# 14_-_LTC3676.net
KiCad netlist of a schematic drawn in Altium Designer
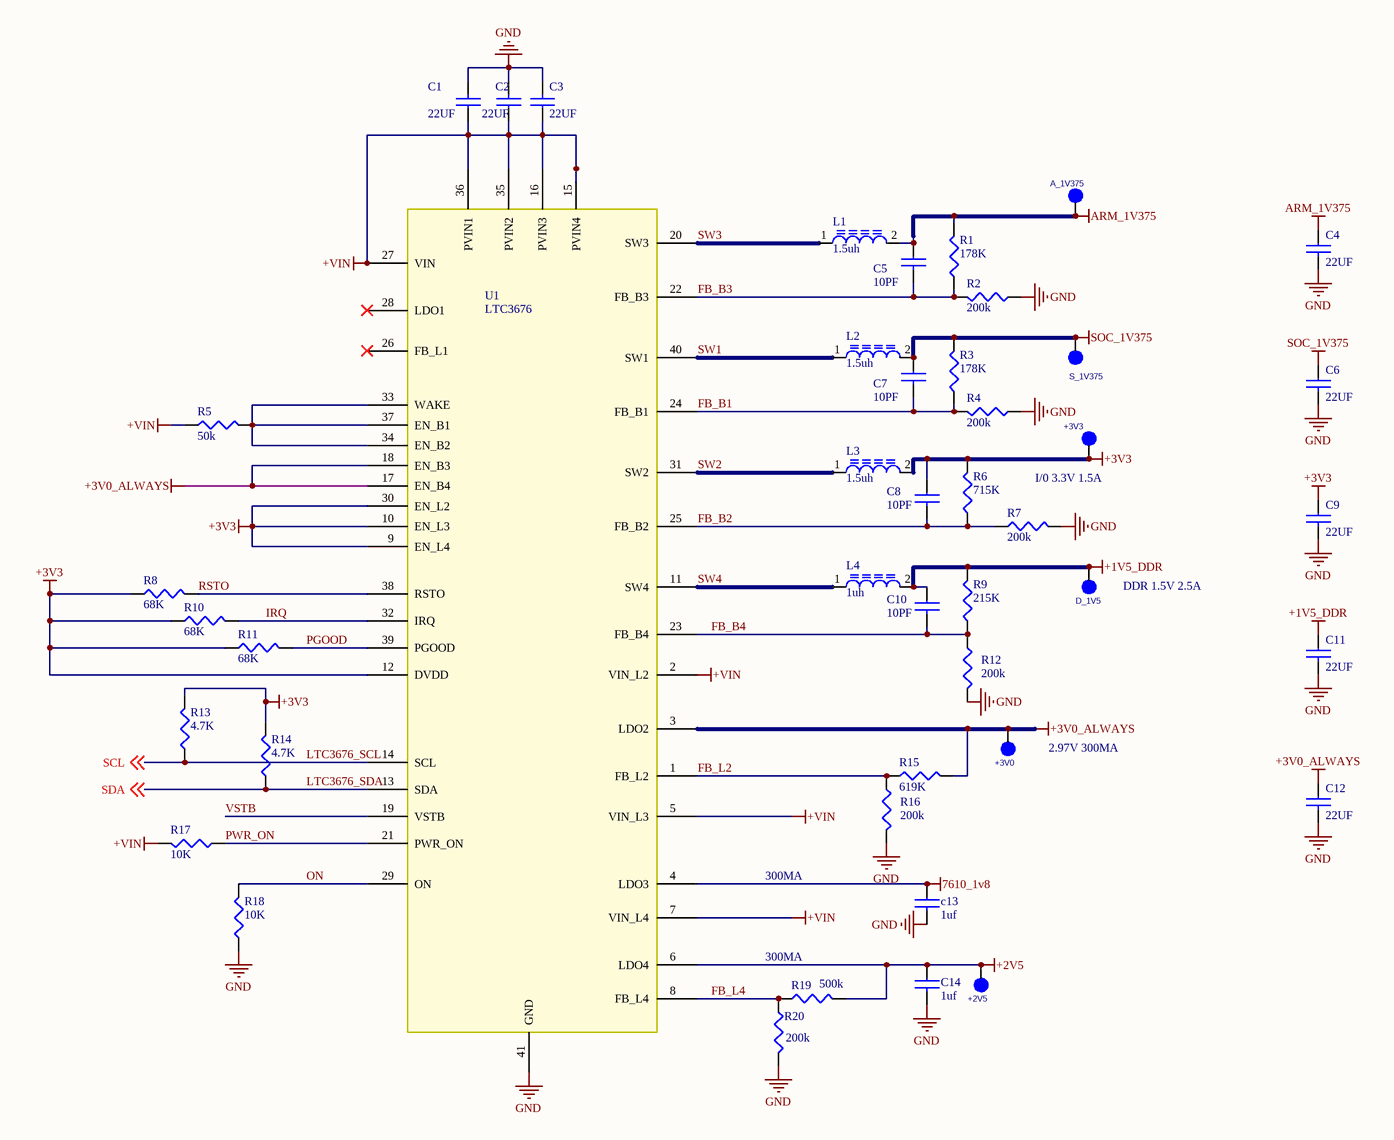
[diagram p0: [14] - LTC3676.SchDoc]

(export (version "E")
  (design (tool "Eeschema 10.0.6"))
  (components
    (comp (ref "+2V5")
      (value "~")
      (description "TEST POINT PAD 0.5MM DIA SMT, NO PART TO ORDER")
      (libsource (lib "*") (part "TESTLOOP"))
    )
    (comp (ref "+3V0")
      (value "~")
      (description "TEST POINT PAD 0.5MM DIA SMT, NO PART TO ORDER")
      (libsource (lib "*") (part "TESTLOOP"))
    )
    (comp (ref "+3V3")
      (value "~")
      (description "TEST POINT PAD 0.5MM DIA SMT, NO PART TO ORDER")
      (libsource (lib "*") (part "TESTLOOP"))
    )
    (comp (ref "A_1V375")
      (value "~")
      (description "TEST POINT PAD 0.5MM DIA SMT, NO PART TO ORDER")
      (libsource (lib "*") (part "TESTLOOP"))
    )
    (comp (ref "C1")
      (value "22UF")
      (footprint "C1206A")
      (description "CAP CER 100UF 10V X5R 20% 1206")
      (fields
        (field (name "MANUFACTURER") "TDK Corporation")
        (field (name "MANUFACTURER PART NUMBER") "C3216X5R1A107M")
      )
      (libsource (lib "Integrated_Library_RF_FEB_2012") (part "C3216X5R1A107M"))
    )
    (comp (ref "C2")
      (value "22UF")
      (footprint "C1206A")
      (description "CAP CER 100UF 10V X5R 20% 1206")
      (fields
        (field (name "MANUFACTURER") "TDK Corporation")
        (field (name "MANUFACTURER PART NUMBER") "C3216X5R1A107M")
      )
      (libsource (lib "Integrated_Library_RF_FEB_2012") (part "C3216X5R1A107M"))
    )
    (comp (ref "C3")
      (value "22UF")
      (footprint "C1206A")
      (description "CAP CER 100UF 10V X5R 20% 1206")
      (fields
        (field (name "MANUFACTURER") "TDK Corporation")
        (field (name "MANUFACTURER PART NUMBER") "C3216X5R1A107M")
      )
      (libsource (lib "Integrated_Library_RF_FEB_2012") (part "C3216X5R1A107M"))
    )
    (comp (ref "C4")
      (value "22UF")
      (footprint "7343CAP")
      (description "CAP CER 100UF 10V X5R 20% 1206")
      (fields
        (field (name "MANUFACTURER") "TDK Corporation")
        (field (name "MANUFACTURER PART NUMBER") "C3216X5R1A107M")
      )
      (libsource (lib "Integrated_Library_RF_FEB_2012") (part "C3216X5R1A107M"))
    )
    (comp (ref "C5")
      (value "10PF")
      (footprint "C0402")
      (description "CAP CER .22UF 25V X5R 20% 0402")
      (fields
        (field (name "MANUFACTURER") "TDK Corporation")
        (field (name "MANUFACTURER PART NUMBER") "C1005X5R1E224M")
      )
      (libsource (lib "Integrated_Library_RF_FEB_2012") (part "C1005X5R1E224M"))
    )
    (comp (ref "C6")
      (value "22UF")
      (footprint "C1206A")
      (description "CAP CER 100UF 10V X5R 20% 1206")
      (fields
        (field (name "MANUFACTURER") "TDK Corporation")
        (field (name "MANUFACTURER PART NUMBER") "C3216X5R1A107M")
      )
      (libsource (lib "Integrated_Library_RF_FEB_2012") (part "C3216X5R1A107M"))
    )
    (comp (ref "C7")
      (value "10PF")
      (footprint "C0402")
      (description "CAP CER .22UF 25V X5R 20% 0402")
      (fields
        (field (name "MANUFACTURER") "TDK Corporation")
        (field (name "MANUFACTURER PART NUMBER") "C1005X5R1E224M")
      )
      (libsource (lib "Integrated_Library_RF_FEB_2012") (part "C1005X5R1E224M"))
    )
    (comp (ref "C8")
      (value "10PF")
      (footprint "C0402")
      (description "CAP CER .22UF 25V X5R 20% 0402")
      (fields
        (field (name "MANUFACTURER") "TDK Corporation")
        (field (name "MANUFACTURER PART NUMBER") "C1005X5R1E224M")
      )
      (libsource (lib "Integrated_Library_RF_FEB_2012") (part "C1005X5R1E224M"))
    )
    (comp (ref "C9")
      (value "22UF")
      (footprint "C1206A")
      (description "CAP CER 100UF 10V X5R 20% 1206")
      (fields
        (field (name "MANUFACTURER") "TDK Corporation")
        (field (name "MANUFACTURER PART NUMBER") "C3216X5R1A107M")
      )
      (libsource (lib "Integrated_Library_RF_FEB_2012") (part "C3216X5R1A107M"))
    )
    (comp (ref "C10")
      (value "10PF")
      (footprint "C0402")
      (description "CAP CER .22UF 25V X5R 20% 0402")
      (fields
        (field (name "MANUFACTURER") "TDK Corporation")
        (field (name "MANUFACTURER PART NUMBER") "C1005X5R1E224M")
      )
      (libsource (lib "Integrated_Library_RF_FEB_2012") (part "C1005X5R1E224M"))
    )
    (comp (ref "C11")
      (value "22UF")
      (footprint "C1206A")
      (description "CAP CER 100UF 10V X5R 20% 1206")
      (fields
        (field (name "MANUFACTURER") "TDK Corporation")
        (field (name "MANUFACTURER PART NUMBER") "C3216X5R1A107M")
      )
      (libsource (lib "Integrated_Library_RF_FEB_2012") (part "C3216X5R1A107M"))
    )
    (comp (ref "C12")
      (value "22UF")
      (footprint "C1206A")
      (description "CAP CER 100UF 10V X5R 20% 1206")
      (fields
        (field (name "MANUFACTURER") "TDK Corporation")
        (field (name "MANUFACTURER PART NUMBER") "C3216X5R1A107M")
      )
      (libsource (lib "Integrated_Library_RF_FEB_2012") (part "C3216X5R1A107M"))
    )
    (comp (ref "c13")
      (value "1uf")
      (footprint "C0402")
      (description "CAP CER .22UF 25V X5R 20% 0402")
      (fields
        (field (name "MANUFACTURER") "TDK Corporation")
        (field (name "MANUFACTURER PART NUMBER") "C1005X5R1E224M")
      )
      (libsource (lib "Integrated_Library_RF_FEB_2012") (part "C1005X5R1E224M"))
    )
    (comp (ref "C14")
      (value "1uf")
      (footprint "C0402")
      (description "CAP CER .22UF 25V X5R 20% 0402")
      (fields
        (field (name "MANUFACTURER") "TDK Corporation")
        (field (name "MANUFACTURER PART NUMBER") "C1005X5R1E224M")
      )
      (libsource (lib "Integrated_Library_RF_FEB_2012") (part "C1005X5R1E224M"))
    )
    (comp (ref "D_1V5")
      (value "~")
      (description "TEST POINT PAD 0.5MM DIA SMT, NO PART TO ORDER")
      (libsource (lib "*") (part "TESTLOOP"))
    )
    (comp (ref "L1")
      (value "1.5uh")
      (footprint "VLCF4020")
      (description "INDUCTOR POWER 10UH .85A SMD")
      (fields
        (field (name "MANUFACTURER") "TDK Corporation")
        (field (name "MANUFACTURER PART NUMBER") "VLCF4020T-100MR85")
        (field (name ".CREATOR") "MM")
        (field (name ".CHECKED PCB") "MM, checked by RF")
        (field (name ".CHECKED SCH") "MM, checked by RF")
      )
      (libsource (lib "Schlib_RF") (part "VLCF4020T-100MR85"))
    )
    (comp (ref "L2")
      (value "1.5uh")
      (footprint "VLCF4020")
      (description "INDUCTOR POWER 10UH .85A SMD")
      (fields
        (field (name "MANUFACTURER") "TDK Corporation")
        (field (name "MANUFACTURER PART NUMBER") "VLCF4020T-100MR85")
        (field (name ".CREATOR") "MM")
        (field (name ".CHECKED PCB") "MM, checked by RF")
        (field (name ".CHECKED SCH") "MM, checked by RF")
      )
      (libsource (lib "Schlib_RF") (part "VLCF4020T-100MR85"))
    )
    (comp (ref "L3")
      (value "1.5uh")
      (footprint "VLCF4020")
      (description "INDUCTOR POWER 10UH .85A SMD")
      (fields
        (field (name "MANUFACTURER") "TDK Corporation")
        (field (name "MANUFACTURER PART NUMBER") "VLCF4020T-100MR85")
        (field (name ".CREATOR") "MM")
        (field (name ".CHECKED PCB") "MM, checked by RF")
        (field (name ".CHECKED SCH") "MM, checked by RF")
      )
      (libsource (lib "Schlib_RF") (part "VLCF4020T-100MR85"))
    )
    (comp (ref "L4")
      (value "1uh")
      (footprint "VLCF4020")
      (description "INDUCTOR POWER 10UH .85A SMD")
      (fields
        (field (name "MANUFACTURER") "TDK Corporation")
        (field (name "MANUFACTURER PART NUMBER") "VLCF4020T-100MR85")
        (field (name ".CREATOR") "MM")
        (field (name ".CHECKED PCB") "MM, checked by RF")
        (field (name ".CHECKED SCH") "MM, checked by RF")
      )
      (libsource (lib "Schlib_RF") (part "VLCF4020T-100MR85"))
    )
    (comp (ref "R1")
      (value "178K")
      (footprint "R0402")
      (description "RES 39.0K OHM 1/16W 1% 0402 SMD")
      (fields
        (field (name "MANUFACTURER") "Yageo")
        (field (name "MANUFACTURER PART NUMBER") "RC0402FR-0739KL")
      )
      (libsource (lib "Integrated_Library_RF_FEB_2012") (part "RC0402FR-0739KL"))
    )
    (comp (ref "R2")
      (value "200k")
      (footprint "R0402")
      (description "RES 39.0K OHM 1/16W 1% 0402 SMD")
      (fields
        (field (name "MANUFACTURER") "Yageo")
        (field (name "MANUFACTURER PART NUMBER") "RC0402FR-0739KL")
      )
      (libsource (lib "Integrated_Library_RF_FEB_2012") (part "RC0402FR-0739KL"))
    )
    (comp (ref "R3")
      (value "178K")
      (footprint "R0402")
      (description "RES 39.0K OHM 1/16W 1% 0402 SMD")
      (fields
        (field (name "MANUFACTURER") "Yageo")
        (field (name "MANUFACTURER PART NUMBER") "RC0402FR-0739KL")
      )
      (libsource (lib "Integrated_Library_RF_FEB_2012") (part "RC0402FR-0739KL"))
    )
    (comp (ref "R4")
      (value "200k")
      (footprint "R0402")
      (description "RES 39.0K OHM 1/16W 1% 0402 SMD")
      (fields
        (field (name "MANUFACTURER") "Yageo")
        (field (name "MANUFACTURER PART NUMBER") "RC0402FR-0739KL")
      )
      (libsource (lib "Integrated_Library_RF_FEB_2012") (part "RC0402FR-0739KL"))
    )
    (comp (ref "R5")
      (value "50k")
      (footprint "R0402")
      (description "RES 39.0K OHM 1/16W 1% 0402 SMD")
      (fields
        (field (name "MANUFACTURER") "Yageo")
        (field (name "MANUFACTURER PART NUMBER") "RC0402FR-0739KL")
      )
      (libsource (lib "Integrated_Library_RF_FEB_2012") (part "RC0402FR-0739KL"))
    )
    (comp (ref "R6")
      (value "715K")
      (footprint "R0402")
      (description "RES 39.0K OHM 1/16W 1% 0402 SMD")
      (fields
        (field (name "MANUFACTURER") "Yageo")
        (field (name "MANUFACTURER PART NUMBER") "RC0402FR-0739KL")
      )
      (libsource (lib "Integrated_Library_RF_FEB_2012") (part "RC0402FR-0739KL"))
    )
    (comp (ref "R7")
      (value "200k")
      (footprint "R0402")
      (description "RES 39.0K OHM 1/16W 1% 0402 SMD")
      (fields
        (field (name "MANUFACTURER") "Yageo")
        (field (name "MANUFACTURER PART NUMBER") "RC0402FR-0739KL")
      )
      (libsource (lib "Integrated_Library_RF_FEB_2012") (part "RC0402FR-0739KL"))
    )
    (comp (ref "R8")
      (value "68K")
      (footprint "R0402")
      (description "RES 39.0K OHM 1/16W 1% 0402 SMD")
      (fields
        (field (name "MANUFACTURER") "Yageo")
        (field (name "MANUFACTURER PART NUMBER") "RC0402FR-0739KL")
      )
      (libsource (lib "Integrated_Library_RF_FEB_2012") (part "RC0402FR-0739KL"))
    )
    (comp (ref "R9")
      (value "215K")
      (footprint "R0402")
      (description "RES 39.0K OHM 1/16W 1% 0402 SMD")
      (fields
        (field (name "MANUFACTURER") "Yageo")
        (field (name "MANUFACTURER PART NUMBER") "RC0402FR-0739KL")
      )
      (libsource (lib "Integrated_Library_RF_FEB_2012") (part "RC0402FR-0739KL"))
    )
    (comp (ref "R10")
      (value "68K")
      (footprint "R0402")
      (description "RES 39.0K OHM 1/16W 1% 0402 SMD")
      (fields
        (field (name "MANUFACTURER") "Yageo")
        (field (name "MANUFACTURER PART NUMBER") "RC0402FR-0739KL")
      )
      (libsource (lib "Integrated_Library_RF_FEB_2012") (part "RC0402FR-0739KL"))
    )
    (comp (ref "R11")
      (value "68K")
      (footprint "R0402")
      (description "RES 39.0K OHM 1/16W 1% 0402 SMD")
      (fields
        (field (name "MANUFACTURER") "Yageo")
        (field (name "MANUFACTURER PART NUMBER") "RC0402FR-0739KL")
      )
      (libsource (lib "Integrated_Library_RF_FEB_2012") (part "RC0402FR-0739KL"))
    )
    (comp (ref "R12")
      (value "200k")
      (footprint "R0402")
      (description "RES 39.0K OHM 1/16W 1% 0402 SMD")
      (fields
        (field (name "MANUFACTURER") "Yageo")
        (field (name "MANUFACTURER PART NUMBER") "RC0402FR-0739KL")
      )
      (libsource (lib "Integrated_Library_RF_FEB_2012") (part "RC0402FR-0739KL"))
    )
    (comp (ref "R13")
      (value "4.7K")
      (footprint "R0402")
      (description "RES 39.0K OHM 1/16W 1% 0402 SMD")
      (fields
        (field (name "MANUFACTURER") "Yageo")
        (field (name "MANUFACTURER PART NUMBER") "RC0402FR-0739KL")
      )
      (libsource (lib "Integrated_Library_RF_FEB_2012") (part "RC0402FR-0739KL"))
    )
    (comp (ref "R14")
      (value "4.7K")
      (footprint "R0402")
      (description "RES 39.0K OHM 1/16W 1% 0402 SMD")
      (fields
        (field (name "MANUFACTURER") "Yageo")
        (field (name "MANUFACTURER PART NUMBER") "RC0402FR-0739KL")
      )
      (libsource (lib "Integrated_Library_RF_FEB_2012") (part "RC0402FR-0739KL"))
    )
    (comp (ref "R15")
      (value "619K")
      (footprint "R0402")
      (description "RES 39.0K OHM 1/16W 1% 0402 SMD")
      (fields
        (field (name "MANUFACTURER") "Yageo")
        (field (name "MANUFACTURER PART NUMBER") "RC0402FR-0739KL")
      )
      (libsource (lib "Integrated_Library_RF_FEB_2012") (part "RC0402FR-0739KL"))
    )
    (comp (ref "R16")
      (value "200k")
      (footprint "R0402")
      (description "RES 39.0K OHM 1/16W 1% 0402 SMD")
      (fields
        (field (name "MANUFACTURER") "Yageo")
        (field (name "MANUFACTURER PART NUMBER") "RC0402FR-0739KL")
      )
      (libsource (lib "Integrated_Library_RF_FEB_2012") (part "RC0402FR-0739KL"))
    )
    (comp (ref "R17")
      (value "10K")
      (footprint "R0402")
      (description "RES 39.0K OHM 1/16W 1% 0402 SMD")
      (fields
        (field (name "MANUFACTURER") "Yageo")
        (field (name "MANUFACTURER PART NUMBER") "RC0402FR-0739KL")
      )
      (libsource (lib "Integrated_Library_RF_FEB_2012") (part "RC0402FR-0739KL"))
    )
    (comp (ref "R18")
      (value "10K")
      (footprint "R0402")
      (description "RES 39.0K OHM 1/16W 1% 0402 SMD")
      (fields
        (field (name "MANUFACTURER") "Yageo")
        (field (name "MANUFACTURER PART NUMBER") "RC0402FR-0739KL")
      )
      (libsource (lib "Integrated_Library_RF_FEB_2012") (part "RC0402FR-0739KL"))
    )
    (comp (ref "R19")
      (value "500k")
      (footprint "R0402")
      (description "RES 39.0K OHM 1/16W 1% 0402 SMD")
      (fields
        (field (name "MANUFACTURER") "Yageo")
        (field (name "MANUFACTURER PART NUMBER") "RC0402FR-0739KL")
      )
      (libsource (lib "Integrated_Library_RF_FEB_2012") (part "RC0402FR-0739KL"))
    )
    (comp (ref "R20")
      (value "200k")
      (footprint "R0402")
      (description "RES 39.0K OHM 1/16W 1% 0402 SMD")
      (fields
        (field (name "MANUFACTURER") "Yageo")
        (field (name "MANUFACTURER PART NUMBER") "RC0402FR-0739KL")
      )
      (libsource (lib "Integrated_Library_RF_FEB_2012") (part "RC0402FR-0739KL"))
    )
    (comp (ref "S_1V375")
      (value "~")
      (description "TEST POINT PAD 0.5MM DIA SMT, NO PART TO ORDER")
      (libsource (lib "*") (part "TESTLOOP"))
    )
    (comp (ref "U1") (value "LTC3676") (footprint "qfn40") (libsource (lib "hack") (part "LTC3676")))
  )
  (nets
    (net (code "1") (name "+1V5_DDR") (class "Default")
      (node (ref "C10") (pin "1") (pinfunction "1_1") (pintype "passive"))
      (node (ref "C11") (pin "1") (pinfunction "1_1") (pintype "passive"))
      (node (ref "D_1V5") (pin "1") (pinfunction "Pin1_1") (pintype "passive"))
      (node (ref "L4") (pin "2") (pinfunction "2_2") (pintype "passive"))
      (node (ref "R9") (pin "2") (pinfunction "2_2") (pintype "passive"))
    )
    (net (code "2") (name "+2V5") (class "Default")
      (node (ref "+2V5") (pin "1") (pinfunction "Pin1_1") (pintype "passive"))
      (node (ref "C14") (pin "1") (pinfunction "1_1") (pintype "passive"))
      (node (ref "R19") (pin "2") (pinfunction "2_2") (pintype "passive"))
      (node (ref "U1") (pin "6") (pinfunction "LDO4_6") (pintype "passive"))
    )
    (net (code "3") (name "+3V0_ALWAYS") (class "Default")
      (node (ref "+3V0") (pin "1") (pinfunction "Pin1_1") (pintype "passive"))
      (node (ref "C12") (pin "1") (pinfunction "1_1") (pintype "passive"))
      (node (ref "R15") (pin "2") (pinfunction "2_2") (pintype "passive"))
      (node (ref "U1") (pin "17") (pinfunction "EN_B4_17") (pintype "passive"))
      (node (ref "U1") (pin "18") (pinfunction "EN_B3_18") (pintype "passive"))
      (node (ref "U1") (pin "3") (pinfunction "LDO2_3") (pintype "passive"))
    )
    (net (code "4") (name "+3V3") (class "Default")
      (node (ref "+3V3") (pin "1") (pinfunction "Pin1_1") (pintype "passive"))
      (node (ref "C8") (pin "1") (pinfunction "1_1") (pintype "passive"))
      (node (ref "C9") (pin "1") (pinfunction "1_1") (pintype "passive"))
      (node (ref "L3") (pin "2") (pinfunction "2_2") (pintype "passive"))
      (node (ref "R10") (pin "1") (pinfunction "1_1") (pintype "passive"))
      (node (ref "R11") (pin "1") (pinfunction "1_1") (pintype "passive"))
      (node (ref "R13") (pin "2") (pinfunction "2_2") (pintype "passive"))
      (node (ref "R14") (pin "2") (pinfunction "2_2") (pintype "passive"))
      (node (ref "R6") (pin "2") (pinfunction "2_2") (pintype "passive"))
      (node (ref "R8") (pin "1") (pinfunction "1_1") (pintype "passive"))
      (node (ref "U1") (pin "10") (pinfunction "EN_L3_10") (pintype "passive"))
      (node (ref "U1") (pin "12") (pinfunction "DVDD_12") (pintype "passive"))
      (node (ref "U1") (pin "30") (pinfunction "EN_L2_30") (pintype "passive"))
      (node (ref "U1") (pin "9") (pinfunction "EN_L4_9") (pintype "passive"))
    )
    (net (code "5") (name "+VIN") (class "Default")
      (node (ref "C1") (pin "1") (pinfunction "1_1") (pintype "passive"))
      (node (ref "C2") (pin "1") (pinfunction "1_1") (pintype "passive"))
      (node (ref "C3") (pin "1") (pinfunction "1_1") (pintype "passive"))
      (node (ref "R17") (pin "2") (pinfunction "2_2") (pintype "passive"))
      (node (ref "R5") (pin "1") (pinfunction "1_1") (pintype "passive"))
      (node (ref "U1") (pin "15") (pinfunction "PVIN4_15") (pintype "passive"))
      (node (ref "U1") (pin "16") (pinfunction "PVIN3_16") (pintype "passive"))
      (node (ref "U1") (pin "2") (pinfunction "VIN_L2_2") (pintype "passive"))
      (node (ref "U1") (pin "27") (pinfunction "VIN_27") (pintype "passive"))
      (node (ref "U1") (pin "35") (pinfunction "PVIN2_35") (pintype "passive"))
      (node (ref "U1") (pin "36") (pinfunction "PVIN1_36") (pintype "passive"))
      (node (ref "U1") (pin "5") (pinfunction "VIN_L3_5") (pintype "passive"))
      (node (ref "U1") (pin "7") (pinfunction "VIN_L4_7") (pintype "passive"))
    )
    (net (code "6") (name "/FB_B1") (class "Default")
      (node (ref "C7") (pin "2") (pinfunction "2_2") (pintype "passive"))
      (node (ref "R3") (pin "1") (pinfunction "1_1") (pintype "passive"))
      (node (ref "R4") (pin "2") (pinfunction "2_2") (pintype "passive"))
      (node (ref "U1") (pin "24") (pinfunction "FB_B1_24") (pintype "passive"))
    )
    (net (code "7") (name "/FB_B2") (class "Default")
      (node (ref "C8") (pin "2") (pinfunction "2_2") (pintype "passive"))
      (node (ref "R6") (pin "1") (pinfunction "1_1") (pintype "passive"))
      (node (ref "R7") (pin "1") (pinfunction "1_1") (pintype "passive"))
      (node (ref "U1") (pin "25") (pinfunction "FB_B2_25") (pintype "passive"))
    )
    (net (code "8") (name "/FB_B3") (class "Default")
      (node (ref "C5") (pin "2") (pinfunction "2_2") (pintype "passive"))
      (node (ref "R1") (pin "1") (pinfunction "1_1") (pintype "passive"))
      (node (ref "R2") (pin "2") (pinfunction "2_2") (pintype "passive"))
      (node (ref "U1") (pin "22") (pinfunction "FB_B3_22") (pintype "passive"))
    )
    (net (code "9") (name "/FB_B4") (class "Default")
      (node (ref "C10") (pin "2") (pinfunction "2_2") (pintype "passive"))
      (node (ref "R12") (pin "1") (pinfunction "1_1") (pintype "passive"))
      (node (ref "R9") (pin "1") (pinfunction "1_1") (pintype "passive"))
      (node (ref "U1") (pin "23") (pinfunction "FB_B4_23") (pintype "passive"))
    )
    (net (code "10") (name "/FB_L2") (class "Default")
      (node (ref "R15") (pin "1") (pinfunction "1_1") (pintype "passive"))
      (node (ref "R16") (pin "1") (pinfunction "1_1") (pintype "passive"))
      (node (ref "U1") (pin "1") (pinfunction "FB_L2_1") (pintype "passive"))
    )
    (net (code "11") (name "/FB_L4") (class "Default")
      (node (ref "R19") (pin "1") (pinfunction "1_1") (pintype "passive"))
      (node (ref "R20") (pin "1") (pinfunction "1_1") (pintype "passive"))
      (node (ref "U1") (pin "8") (pinfunction "FB_L4_8") (pintype "passive"))
    )
    (net (code "12") (name "/IRQ") (class "Default")
      (node (ref "R10") (pin "2") (pinfunction "2_2") (pintype "passive"))
      (node (ref "U1") (pin "32") (pinfunction "IRQ_32") (pintype "passive"))
    )
    (net (code "13") (name "/ON") (class "Default")
      (node (ref "R18") (pin "2") (pinfunction "2_2") (pintype "passive"))
      (node (ref "U1") (pin "29") (pinfunction "ON_29") (pintype "passive"))
    )
    (net (code "14") (name "/PGOOD") (class "Default")
      (node (ref "R11") (pin "2") (pinfunction "2_2") (pintype "passive"))
      (node (ref "U1") (pin "39") (pinfunction "PGOOD_39") (pintype "passive"))
    )
    (net (code "15") (name "/PWR_ON") (class "Default")
      (node (ref "R17") (pin "1") (pinfunction "1_1") (pintype "passive"))
      (node (ref "U1") (pin "21") (pinfunction "PWR_ON_21") (pintype "passive"))
    )
    (net (code "16") (name "/RSTO") (class "Default")
      (node (ref "R8") (pin "2") (pinfunction "2_2") (pintype "passive"))
      (node (ref "U1") (pin "38") (pinfunction "RSTO_38") (pintype "passive"))
    )
    (net (code "17") (name "/SW1") (class "Default")
      (node (ref "L2") (pin "1") (pinfunction "1_1") (pintype "passive"))
      (node (ref "U1") (pin "40") (pinfunction "SW1_40") (pintype "passive"))
    )
    (net (code "18") (name "/SW2") (class "Default")
      (node (ref "L3") (pin "1") (pinfunction "1_1") (pintype "passive"))
      (node (ref "U1") (pin "31") (pinfunction "SW2_31") (pintype "passive"))
    )
    (net (code "19") (name "/SW3") (class "Default")
      (node (ref "L1") (pin "1") (pinfunction "1_1") (pintype "passive"))
      (node (ref "U1") (pin "20") (pinfunction "SW3_20") (pintype "passive"))
    )
    (net (code "20") (name "/SW4") (class "Default")
      (node (ref "L4") (pin "1") (pinfunction "1_1") (pintype "passive"))
      (node (ref "U1") (pin "11") (pinfunction "SW4_11") (pintype "passive"))
    )
    (net (code "21") (name "/VSTB") (class "Default")
      (node (ref "U1") (pin "19") (pinfunction "VSTB_19") (pintype "passive"))
    )
    (net (code "22") (name "7610_1v8") (class "Default")
      (node (ref "U1") (pin "4") (pinfunction "LDO3_4") (pintype "passive"))
      (node (ref "c13") (pin "1") (pinfunction "1_1") (pintype "passive"))
    )
    (net (code "23") (name "ARM_1V375") (class "Default")
      (node (ref "A_1V375") (pin "1") (pinfunction "Pin1_1") (pintype "passive"))
      (node (ref "C4") (pin "1") (pinfunction "1_1") (pintype "passive"))
      (node (ref "C5") (pin "1") (pinfunction "1_1") (pintype "passive"))
      (node (ref "L1") (pin "2") (pinfunction "2_2") (pintype "passive"))
      (node (ref "R1") (pin "2") (pinfunction "2_2") (pintype "passive"))
    )
    (net (code "24") (name "GND") (class "Default")
      (node (ref "C1") (pin "2") (pinfunction "2_2") (pintype "passive"))
      (node (ref "C11") (pin "2") (pinfunction "2_2") (pintype "passive"))
      (node (ref "C12") (pin "2") (pinfunction "2_2") (pintype "passive"))
      (node (ref "C14") (pin "2") (pinfunction "2_2") (pintype "passive"))
      (node (ref "C2") (pin "2") (pinfunction "2_2") (pintype "passive"))
      (node (ref "C3") (pin "2") (pinfunction "2_2") (pintype "passive"))
      (node (ref "C4") (pin "2") (pinfunction "2_2") (pintype "passive"))
      (node (ref "C6") (pin "2") (pinfunction "2_2") (pintype "passive"))
      (node (ref "C9") (pin "2") (pinfunction "2_2") (pintype "passive"))
      (node (ref "R12") (pin "2") (pinfunction "2_2") (pintype "passive"))
      (node (ref "R16") (pin "2") (pinfunction "2_2") (pintype "passive"))
      (node (ref "R18") (pin "1") (pinfunction "1_1") (pintype "passive"))
      (node (ref "R2") (pin "1") (pinfunction "1_1") (pintype "passive"))
      (node (ref "R20") (pin "2") (pinfunction "2_2") (pintype "passive"))
      (node (ref "R4") (pin "1") (pinfunction "1_1") (pintype "passive"))
      (node (ref "R7") (pin "2") (pinfunction "2_2") (pintype "passive"))
      (node (ref "U1") (pin "41") (pinfunction "GND_41") (pintype "passive"))
      (node (ref "c13") (pin "2") (pinfunction "2_2") (pintype "passive"))
    )
    (net (code "25") (name "Net-(U1-EN_B1)") (class "Default")
      (node (ref "R5") (pin "2") (pinfunction "2_2") (pintype "passive"))
      (node (ref "U1") (pin "33") (pinfunction "WAKE_33") (pintype "passive"))
      (node (ref "U1") (pin "34") (pinfunction "EN_B2_34") (pintype "passive"))
      (node (ref "U1") (pin "37") (pinfunction "EN_B1_37") (pintype "passive"))
    )
    (net (code "26") (name "SCL") (class "Default")
      (node (ref "R13") (pin "1") (pinfunction "1_1") (pintype "passive"))
      (node (ref "U1") (pin "14") (pinfunction "SCL_14") (pintype "passive"))
    )
    (net (code "27") (name "SDA") (class "Default")
      (node (ref "R14") (pin "1") (pinfunction "1_1") (pintype "passive"))
      (node (ref "U1") (pin "13") (pinfunction "SDA_13") (pintype "passive"))
    )
    (net (code "28") (name "SOC_1V375") (class "Default")
      (node (ref "C6") (pin "1") (pinfunction "1_1") (pintype "passive"))
      (node (ref "C7") (pin "1") (pinfunction "1_1") (pintype "passive"))
      (node (ref "L2") (pin "2") (pinfunction "2_2") (pintype "passive"))
      (node (ref "R3") (pin "2") (pinfunction "2_2") (pintype "passive"))
      (node (ref "S_1V375") (pin "1") (pinfunction "Pin1_1") (pintype "passive"))
    )
    (net (code "29") (name "unconnected-(U1-FB_L1-Pad26)") (class "Default")
      (node (ref "U1") (pin "26") (pinfunction "FB_L1_26") (pintype "passive+no_connect"))
    )
    (net (code "30") (name "unconnected-(U1-LDO1-Pad28)") (class "Default")
      (node (ref "U1") (pin "28") (pinfunction "LDO1_28") (pintype "passive+no_connect"))
    )
  )
)
